# Omniboard.net
KiCad netlist of a schematic drawn in EAGLE
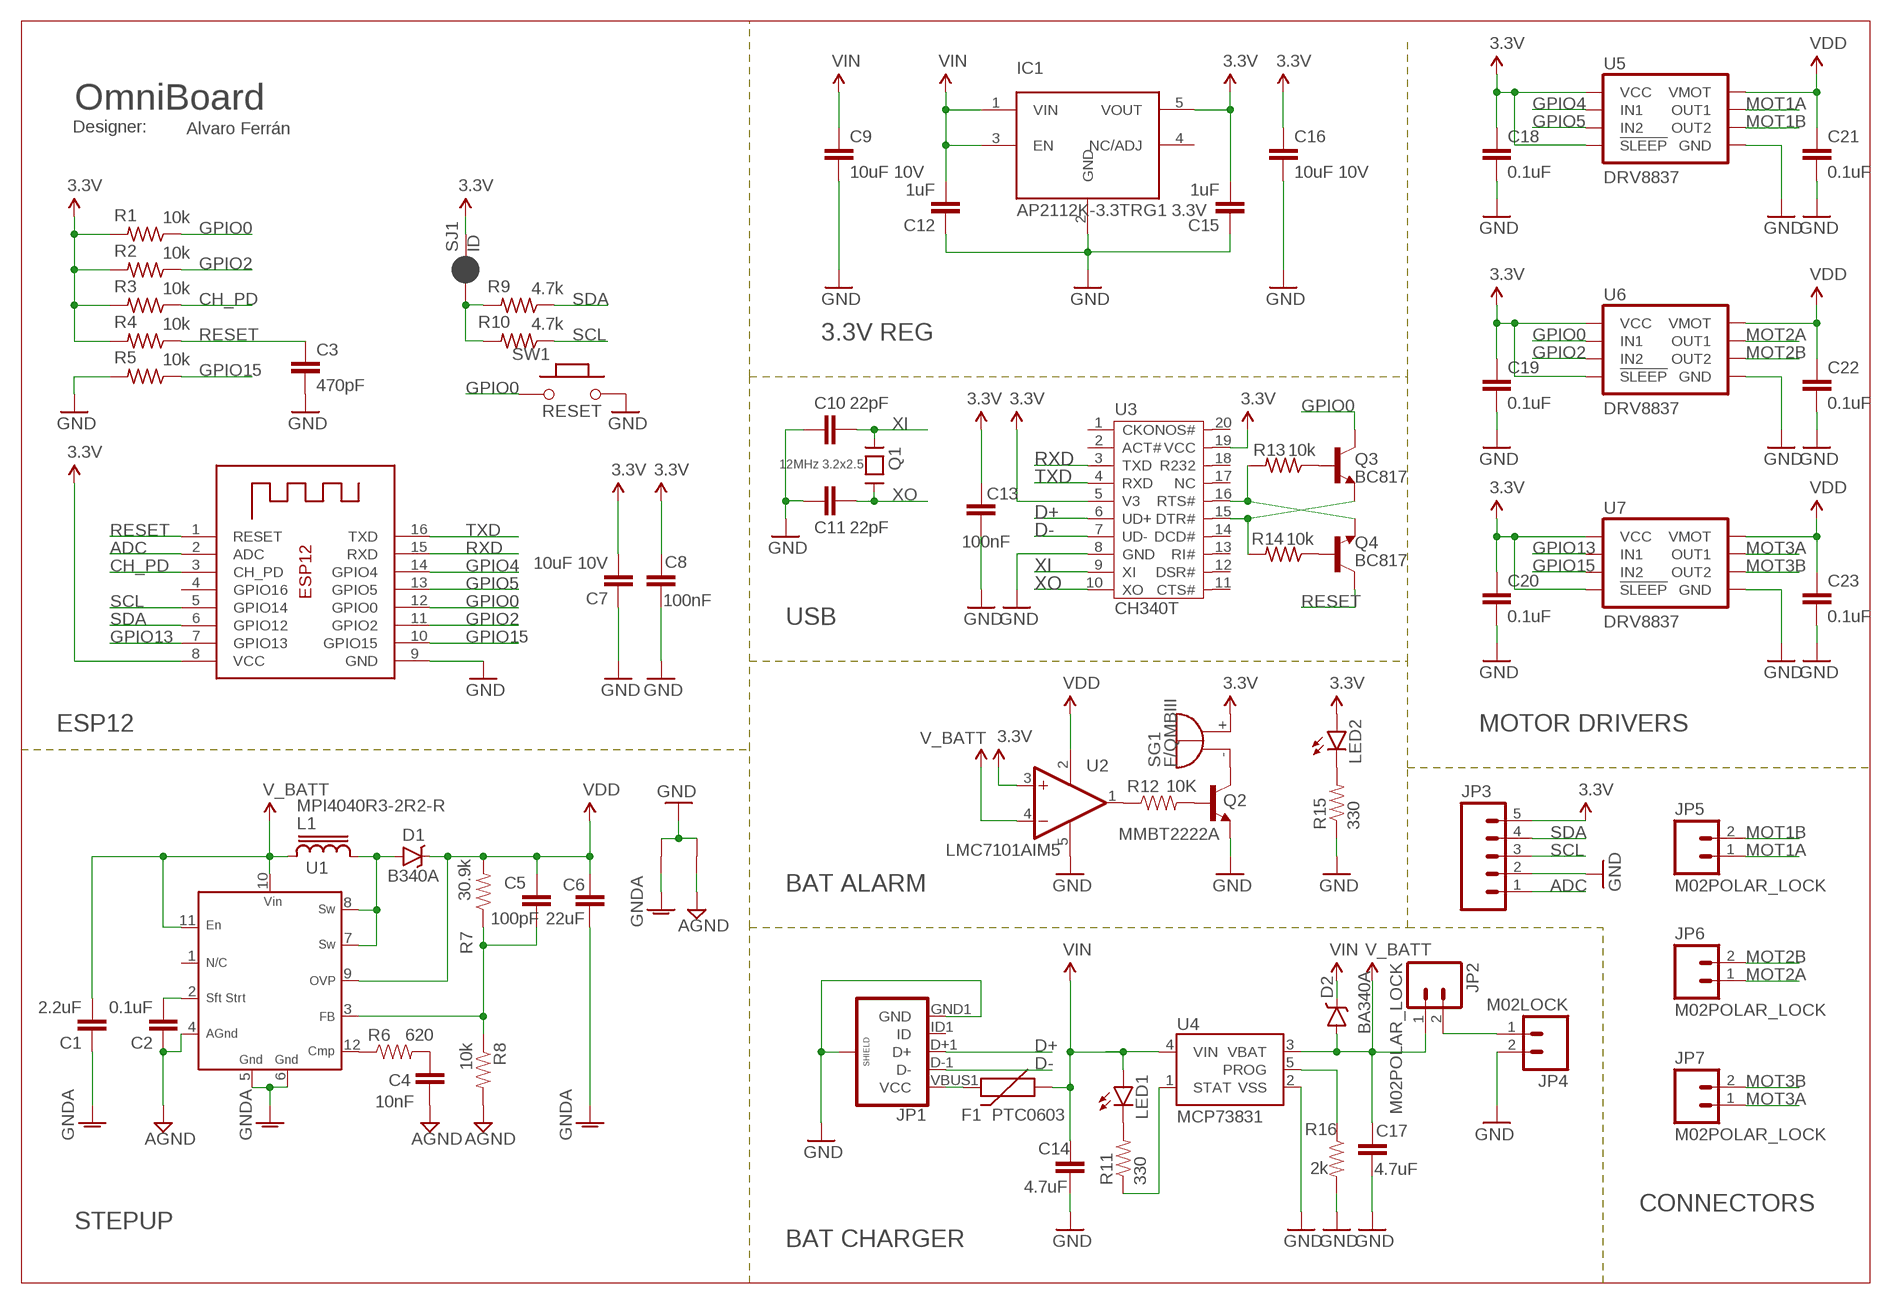
[diagram p0: schematic, sheet 1]

(export (version "E")
  (design (tool "Eeschema 10.0.6"))
  (components
    (comp (ref "C1")
      (value "2.2uF")
      (footprint "eagle-import:0603-CAP")
      (libsource (lib "eagle-import") (part "CAP0603-CAP"))
    )
    (comp (ref "C2")
      (value "0.1uF")
      (footprint "eagle-import:0603-CAP")
      (libsource (lib "eagle-import") (part "CAP0603-CAP"))
    )
    (comp (ref "C3")
      (value "470pF")
      (footprint "eagle-import:0402-CAP")
      (libsource (lib "eagle-import") (part "CAP0402-CAP"))
    )
    (comp (ref "C4")
      (value "10nF")
      (footprint "eagle-import:0603-CAP")
      (libsource (lib "eagle-import") (part "CAP0603-CAP"))
    )
    (comp (ref "C5")
      (value "100pF")
      (footprint "eagle-import:0603-CAP")
      (libsource (lib "eagle-import") (part "CAP0603-CAP"))
    )
    (comp (ref "C6")
      (value "22uF")
      (footprint "eagle-import:0805")
      (libsource (lib "eagle-import") (part "22UF-6.3V-20%(0805)"))
    )
    (comp (ref "C7")
      (value "10uF 10V")
      (footprint "eagle-import:0402-CAP")
      (libsource (lib "eagle-import") (part "CAP0402-CAP"))
    )
    (comp (ref "C8")
      (value "100nF")
      (footprint "eagle-import:0402-CAP")
      (libsource (lib "eagle-import") (part "CAP0402-CAP"))
    )
    (comp (ref "C9")
      (value "10uF 10V")
      (footprint "eagle-import:0603-CAP")
      (libsource (lib "eagle-import") (part "CAP0603-CAP"))
    )
    (comp (ref "C10")
      (value "22pF")
      (footprint "eagle-import:0402-CAP")
      (libsource (lib "eagle-import") (part "CAP0402-CAP"))
    )
    (comp (ref "C11")
      (value "22pF")
      (footprint "eagle-import:0402-CAP")
      (libsource (lib "eagle-import") (part "CAP0402-CAP"))
    )
    (comp (ref "C12")
      (value "1uF")
      (footprint "eagle-import:0603-CAP")
      (libsource (lib "eagle-import") (part "CAP0603-CAP"))
    )
    (comp (ref "C13")
      (value "100nF")
      (footprint "eagle-import:0402-CAP")
      (libsource (lib "eagle-import") (part "CAP0402-CAP"))
    )
    (comp (ref "C14")
      (value "4.7uF")
      (footprint "eagle-import:0402-CAP")
      (libsource (lib "eagle-import") (part "CAP0402-CAP"))
    )
    (comp (ref "C15")
      (value "1uF")
      (footprint "eagle-import:0603-CAP")
      (libsource (lib "eagle-import") (part "CAP0603-CAP"))
    )
    (comp (ref "C16")
      (value "10uF 10V")
      (footprint "eagle-import:0603-CAP")
      (libsource (lib "eagle-import") (part "CAP0603-CAP"))
    )
    (comp (ref "C17")
      (value "4.7uF")
      (footprint "eagle-import:0402-CAP")
      (libsource (lib "eagle-import") (part "CAP0402-CAP"))
    )
    (comp (ref "C18")
      (value "0.1uF")
      (footprint "eagle-import:0402-CAP")
      (libsource (lib "eagle-import") (part "0.1UF-16V(+-10%)(0402)"))
    )
    (comp (ref "C19")
      (value "0.1uF")
      (footprint "eagle-import:0402-CAP")
      (libsource (lib "eagle-import") (part "0.1UF-16V(+-10%)(0402)"))
    )
    (comp (ref "C20")
      (value "0.1uF")
      (footprint "eagle-import:0402-CAP")
      (libsource (lib "eagle-import") (part "0.1UF-16V(+-10%)(0402)"))
    )
    (comp (ref "C21")
      (value "0.1uF")
      (footprint "eagle-import:0402-CAP")
      (libsource (lib "eagle-import") (part "0.1UF-16V(+-10%)(0402)"))
    )
    (comp (ref "C22")
      (value "0.1uF")
      (footprint "eagle-import:0402-CAP")
      (libsource (lib "eagle-import") (part "0.1UF-16V(+-10%)(0402)"))
    )
    (comp (ref "C23")
      (value "0.1uF")
      (footprint "eagle-import:0402-CAP")
      (libsource (lib "eagle-import") (part "0.1UF-16V(+-10%)(0402)"))
    )
    (comp (ref "D1")
      (value "B340A")
      (footprint "eagle-import:SMA-DIODE")
      (libsource (lib "eagle-import") (part "DIODE-SCHOTTKY-B340A"))
    )
    (comp (ref "D2")
      (value "BA340A")
      (footprint "eagle-import:SMA-DIODE")
      (libsource (lib "eagle-import") (part "B340A"))
    )
    (comp (ref "F1")
      (value "PTC0603")
      (footprint "eagle-import:0603")
      (libsource (lib "eagle-import") (part "PTC0603"))
    )
    (comp (ref "GND10")
      (value "VIRTUAL_GND")
      (footprint "eagle-import:STARGND")
      (libsource (lib "eagle-import") (part "VIRTUAL_GND"))
    )
    (comp (ref "GND13")
      (value "VIRTUAL_GND")
      (footprint "eagle-import:STARGND")
      (libsource (lib "eagle-import") (part "VIRTUAL_GND"))
    )
    (comp (ref "IC1")
      (value "AP2112K-3.3TRG1 3.3V")
      (footprint "eagle-import:SOT23-5")
      (libsource (lib "eagle-import") (part "5PIN_REG"))
    )
    (comp (ref "JP1")
      (value "USB_MICROB")
      (footprint "eagle-import:USB-B-MICRO-SMD_V03")
      (libsource (lib "eagle-import") (part "USB_MICROB_PLUGCONN-11752"))
    )
    (comp (ref "JP2")
      (value "M02POLAR_LOCK")
      (footprint "eagle-import:MOLEX-1X2_LOCK")
      (libsource (lib "eagle-import") (part "M02POLAR_LOCK"))
    )
    (comp (ref "JP3")
      (value "M05LOCK")
      (footprint "eagle-import:1X05_LOCK")
      (libsource (lib "eagle-import") (part "M05LOCK"))
    )
    (comp (ref "JP4")
      (value "M02LOCK")
      (footprint "eagle-import:1X02_LOCK")
      (libsource (lib "eagle-import") (part "M02LOCK"))
    )
    (comp (ref "JP5")
      (value "M02POLAR_LOCK")
      (footprint "eagle-import:MOLEX-1X2_LOCK")
      (libsource (lib "eagle-import") (part "M02POLAR_LOCK"))
    )
    (comp (ref "JP6")
      (value "M02POLAR_LOCK")
      (footprint "eagle-import:MOLEX-1X2_LOCK")
      (libsource (lib "eagle-import") (part "M02POLAR_LOCK"))
    )
    (comp (ref "JP7")
      (value "M02POLAR_LOCK")
      (footprint "eagle-import:MOLEX-1X2_LOCK")
      (libsource (lib "eagle-import") (part "M02POLAR_LOCK"))
    )
    (comp (ref "L1")
      (value "MPI4040R3-2R2-R")
      (footprint "eagle-import:MPI4040R3-2R2-R")
      (libsource (lib "eagle-import") (part "MPI4040R3-2R2-R"))
    )
    (comp (ref "LED1")
      (value "LED0603")
      (footprint "eagle-import:LED-0603")
      (libsource (lib "eagle-import") (part "LED0603"))
    )
    (comp (ref "LED2")
      (value "LED0603")
      (footprint "eagle-import:LED-0603")
      (libsource (lib "eagle-import") (part "LED0603"))
    )
    (comp (ref "Q1")
      (value "12MHz 3.2x2.5")
      (footprint "eagle-import:CRYSTAL_3.2X2.5")
      (libsource (lib "eagle-import") (part "CRYSTAL3.2X2.5"))
    )
    (comp (ref "Q2")
      (value "MMBT2222A")
      (footprint "eagle-import:SOT23-3")
      (libsource (lib "eagle-import") (part "TRANSISTOR_NPNMMBT2222A"))
    )
    (comp (ref "Q3")
      (value "BC817")
      (footprint "eagle-import:SOT23-BEC")
      (libsource (lib "eagle-import") (part "BC817SMD-16"))
    )
    (comp (ref "Q4")
      (value "BC817")
      (footprint "eagle-import:SOT23-BEC")
      (libsource (lib "eagle-import") (part "BC817SMD-16"))
    )
    (comp (ref "R1")
      (value "10k")
      (footprint "eagle-import:R0402")
      (libsource (lib "eagle-import") (part "R-US_R0402"))
    )
    (comp (ref "R2")
      (value "10k")
      (footprint "eagle-import:R0402")
      (libsource (lib "eagle-import") (part "R-US_R0402"))
    )
    (comp (ref "R3")
      (value "10k")
      (footprint "eagle-import:R0402")
      (libsource (lib "eagle-import") (part "R-US_R0402"))
    )
    (comp (ref "R4")
      (value "10k")
      (footprint "eagle-import:R0402")
      (libsource (lib "eagle-import") (part "R-US_R0402"))
    )
    (comp (ref "R5")
      (value "10k")
      (footprint "eagle-import:R0402")
      (libsource (lib "eagle-import") (part "R-US_R0402"))
    )
    (comp (ref "R6")
      (value "620")
      (footprint "eagle-import:0603-RES")
      (libsource (lib "eagle-import") (part "SparkFun-Passives_RESISTOR0603-RES"))
    )
    (comp (ref "R7")
      (value "30.9k")
      (footprint "eagle-import:0603-RES")
      (libsource (lib "eagle-import") (part "SparkFun-Passives_RESISTOR0603-RES"))
    )
    (comp (ref "R8")
      (value "10k")
      (footprint "eagle-import:0603-RES")
      (libsource (lib "eagle-import") (part "SparkFun-Passives_RESISTOR0603-RES"))
    )
    (comp (ref "R9")
      (value "4.7k")
      (footprint "eagle-import:R0402")
      (libsource (lib "eagle-import") (part "R-US_R0402"))
    )
    (comp (ref "R10")
      (value "4.7k")
      (footprint "eagle-import:R0402")
      (libsource (lib "eagle-import") (part "R-US_R0402"))
    )
    (comp (ref "R11")
      (value "330")
      (footprint "eagle-import:0402-RES")
      (libsource (lib "eagle-import") (part "SparkFun-Passives_RESISTOR0402-RES"))
    )
    (comp (ref "R12")
      (value "10K")
      (footprint "eagle-import:0402-RES")
      (libsource (lib "eagle-import") (part "RESISTOR0402-RES"))
    )
    (comp (ref "R13")
      (value "10k")
      (footprint "eagle-import:R0402")
      (libsource (lib "eagle-import") (part "R-US_R0402"))
    )
    (comp (ref "R14")
      (value "10k")
      (footprint "eagle-import:R0402")
      (libsource (lib "eagle-import") (part "R-US_R0402"))
    )
    (comp (ref "R15")
      (value "330")
      (footprint "eagle-import:0402-RES")
      (libsource (lib "eagle-import") (part "SparkFun-Passives_RESISTOR0402-RES"))
    )
    (comp (ref "R16")
      (value "2k")
      (footprint "eagle-import:0402-RES")
      (libsource (lib "eagle-import") (part "SparkFun-Passives_RESISTOR0402-RES"))
    )
    (comp (ref "SG1")
      (value "F/QMBIII")
      (footprint "eagle-import:F_QMBIII")
      (libsource (lib "eagle-import") (part "F/QMBIII"))
    )
    (comp (ref "SJ1")
      (value "ID")
      (footprint "eagle-import:PAD-JUMPER-2-NC_BY_PASTE_YES_SILK")
      (libsource (lib "eagle-import") (part "JUMPER-PAD-2-NC_BY_PASTE"))
    )
    (comp (ref "SW1")
      (value "RESET")
      (footprint "eagle-import:157SW")
      (libsource (lib "eagle-import") (part "PB157"))
    )
    (comp (ref "U1")
      (value "MIC2253")
      (footprint "eagle-import:MLF12_3.0MM_X_3.0MM")
      (libsource (lib "eagle-import") (part "MIC2253"))
    )
    (comp (ref "U2")
      (value "LMC7101AIM5")
      (footprint "eagle-import:SOT23-5")
      (libsource (lib "eagle-import") (part "LMC7101AIM5"))
    )
    (comp (ref "U3")
      (value "CH340T")
      (footprint "eagle-import:SSOP20")
      (libsource (lib "eagle-import") (part "CH340T"))
    )
    (comp (ref "U4")
      (value "MCP73831")
      (footprint "eagle-import:SOT23-5")
      (libsource (lib "eagle-import") (part "MCP73831"))
    )
    (comp (ref "U5")
      (value "DRV8837")
      (footprint "eagle-import:DSG")
      (libsource (lib "eagle-import") (part "DRV8837"))
    )
    (comp (ref "U6")
      (value "DRV8837")
      (footprint "eagle-import:DSG")
      (libsource (lib "eagle-import") (part "DRV8837"))
    )
    (comp (ref "U7")
      (value "DRV8837")
      (footprint "eagle-import:DSG")
      (libsource (lib "eagle-import") (part "DRV8837"))
    )
    (comp (ref "X1")
      (value "ESP-12")
      (footprint "eagle-import:ESP-12")
      (libsource (lib "eagle-import") (part "ESP-12"))
    )
  )
  (nets
    (net (code "1") (name "/ADC") (class "Default")
      (node (ref "JP3") (pin "1") (pinfunction "1_1") (pintype "passive"))
      (node (ref "X1") (pin "2") (pinfunction "ADC_2") (pintype "passive"))
    )
    (net (code "2") (name "/CH_PD") (class "Default")
      (node (ref "R3") (pin "1") (pinfunction "1_1") (pintype "passive"))
      (node (ref "X1") (pin "3") (pinfunction "CH_PD_3") (pintype "input"))
    )
    (net (code "3") (name "/D+") (class "Default")
      (node (ref "JP1") (pin "D+1") (pinfunction "D+_D+1") (pintype "bidirectional"))
      (node (ref "U3") (pin "6") (pinfunction "UD+_6") (pintype "bidirectional"))
    )
    (net (code "4") (name "/D-") (class "Default")
      (node (ref "JP1") (pin "D-1") (pinfunction "D-_D-1") (pintype "bidirectional"))
      (node (ref "U3") (pin "7") (pinfunction "UD-_7") (pintype "bidirectional"))
    )
    (net (code "5") (name "/GPIO0") (class "Default")
      (node (ref "Q3") (pin "C") (pinfunction "C_C") (pintype "passive"))
      (node (ref "R1") (pin "1") (pinfunction "1_1") (pintype "passive"))
      (node (ref "SW1") (pin "1") (pinfunction "1_1") (pintype "passive"))
      (node (ref "U6") (pin "6") (pinfunction "IN1_6") (pintype "bidirectional"))
      (node (ref "X1") (pin "12") (pinfunction "GPIO0_12") (pintype "bidirectional"))
    )
    (net (code "6") (name "/GPIO2") (class "Default")
      (node (ref "R2") (pin "1") (pinfunction "1_1") (pintype "passive"))
      (node (ref "U6") (pin "5") (pinfunction "IN2_5") (pintype "bidirectional"))
      (node (ref "X1") (pin "11") (pinfunction "GPIO2_11") (pintype "bidirectional"))
    )
    (net (code "7") (name "/GPIO4") (class "Default")
      (node (ref "U5") (pin "6") (pinfunction "IN1_6") (pintype "bidirectional"))
      (node (ref "X1") (pin "14") (pinfunction "GPIO4_14") (pintype "bidirectional"))
    )
    (net (code "8") (name "/GPIO5") (class "Default")
      (node (ref "U5") (pin "5") (pinfunction "IN2_5") (pintype "bidirectional"))
      (node (ref "X1") (pin "13") (pinfunction "GPIO5_13") (pintype "bidirectional"))
    )
    (net (code "9") (name "/GPIO13") (class "Default")
      (node (ref "U7") (pin "6") (pinfunction "IN1_6") (pintype "bidirectional"))
      (node (ref "X1") (pin "7") (pinfunction "GPIO13_7") (pintype "bidirectional"))
    )
    (net (code "10") (name "/GPIO15") (class "Default")
      (node (ref "R5") (pin "1") (pinfunction "1_1") (pintype "passive"))
      (node (ref "U7") (pin "5") (pinfunction "IN2_5") (pintype "bidirectional"))
      (node (ref "X1") (pin "10") (pinfunction "GPIO15_10") (pintype "bidirectional"))
    )
    (net (code "11") (name "/MOT1A") (class "Default")
      (node (ref "JP5") (pin "1") (pinfunction "1_1") (pintype "passive"))
      (node (ref "U5") (pin "2") (pinfunction "OUT1_2") (pintype "bidirectional"))
    )
    (net (code "12") (name "/MOT1B") (class "Default")
      (node (ref "JP5") (pin "2") (pinfunction "2_2") (pintype "passive"))
      (node (ref "U5") (pin "3") (pinfunction "OUT2_3") (pintype "bidirectional"))
    )
    (net (code "13") (name "/MOT2A") (class "Default")
      (node (ref "JP6") (pin "1") (pinfunction "1_1") (pintype "passive"))
      (node (ref "U6") (pin "2") (pinfunction "OUT1_2") (pintype "bidirectional"))
    )
    (net (code "14") (name "/MOT2B") (class "Default")
      (node (ref "JP6") (pin "2") (pinfunction "2_2") (pintype "passive"))
      (node (ref "U6") (pin "3") (pinfunction "OUT2_3") (pintype "bidirectional"))
    )
    (net (code "15") (name "/MOT3A") (class "Default")
      (node (ref "JP7") (pin "1") (pinfunction "1_1") (pintype "passive"))
      (node (ref "U7") (pin "2") (pinfunction "OUT1_2") (pintype "bidirectional"))
    )
    (net (code "16") (name "/MOT3B") (class "Default")
      (node (ref "JP7") (pin "2") (pinfunction "2_2") (pintype "passive"))
      (node (ref "U7") (pin "3") (pinfunction "OUT2_3") (pintype "bidirectional"))
    )
    (net (code "17") (name "/NOS#") (class "Default")
      (node (ref "U3") (pin "20") (pinfunction "NOS#_20") (pintype "power_in"))
    )
    (net (code "18") (name "/RESET") (class "Default")
      (node (ref "C3") (pin "1") (pinfunction "1_1") (pintype "passive"))
      (node (ref "Q4") (pin "C") (pinfunction "C_C") (pintype "passive"))
      (node (ref "R4") (pin "1") (pinfunction "1_1") (pintype "passive"))
      (node (ref "X1") (pin "1") (pinfunction "RESET_1") (pintype "input"))
    )
    (net (code "19") (name "/RXD") (class "Default")
      (node (ref "U3") (pin "3") (pinfunction "TXD_3") (pintype "output"))
      (node (ref "X1") (pin "15") (pinfunction "RXD_15") (pintype "input"))
    )
    (net (code "20") (name "/SCL") (class "Default")
      (node (ref "JP3") (pin "3") (pinfunction "3_3") (pintype "passive"))
      (node (ref "R10") (pin "1") (pinfunction "1_1") (pintype "passive"))
      (node (ref "X1") (pin "5") (pinfunction "GPIO14_5") (pintype "bidirectional"))
    )
    (net (code "21") (name "/SDA") (class "Default")
      (node (ref "JP3") (pin "4") (pinfunction "4_4") (pintype "passive"))
      (node (ref "R9") (pin "1") (pinfunction "1_1") (pintype "passive"))
      (node (ref "X1") (pin "6") (pinfunction "GPIO12_6") (pintype "bidirectional"))
    )
    (net (code "22") (name "/TXD") (class "Default")
      (node (ref "U3") (pin "4") (pinfunction "RXD_4") (pintype "input"))
      (node (ref "X1") (pin "16") (pinfunction "TXD_16") (pintype "output"))
    )
    (net (code "23") (name "/XI") (class "Default")
      (node (ref "C10") (pin "2") (pinfunction "2_2") (pintype "passive"))
      (node (ref "Q1") (pin "3") (pinfunction "P$2_3") (pintype "passive"))
      (node (ref "U3") (pin "9") (pinfunction "XI_9") (pintype "input"))
    )
    (net (code "24") (name "/XO") (class "Default")
      (node (ref "C11") (pin "2") (pinfunction "2_2") (pintype "passive"))
      (node (ref "Q1") (pin "1") (pinfunction "P$1_1") (pintype "passive"))
      (node (ref "U3") (pin "10") (pinfunction "XO_10") (pintype "output"))
    )
    (net (code "25") (name "3.3V") (class "Default")
      (node (ref "C13") (pin "2") (pinfunction "2_2") (pintype "passive"))
      (node (ref "C15") (pin "2") (pinfunction "2_2") (pintype "passive"))
      (node (ref "C16") (pin "1") (pinfunction "1_1") (pintype "passive"))
      (node (ref "C18") (pin "1") (pinfunction "1_1") (pintype "passive"))
      (node (ref "C19") (pin "1") (pinfunction "1_1") (pintype "passive"))
      (node (ref "C20") (pin "1") (pinfunction "1_1") (pintype "passive"))
      (node (ref "C7") (pin "2") (pinfunction "2_2") (pintype "passive"))
      (node (ref "C8") (pin "1") (pinfunction "1_1") (pintype "passive"))
      (node (ref "IC1") (pin "5") (pinfunction "VOUT_5") (pintype "bidirectional"))
      (node (ref "JP3") (pin "5") (pinfunction "5_5") (pintype "passive"))
      (node (ref "LED2") (pin "A") (pinfunction "A_A") (pintype "passive"))
      (node (ref "R1") (pin "2") (pinfunction "2_2") (pintype "passive"))
      (node (ref "R2") (pin "2") (pinfunction "2_2") (pintype "passive"))
      (node (ref "R3") (pin "2") (pinfunction "2_2") (pintype "passive"))
      (node (ref "R4") (pin "2") (pinfunction "2_2") (pintype "passive"))
      (node (ref "SG1") (pin "+") (pinfunction "-_+") (pintype "passive"))
      (node (ref "SJ1") (pin "2") (pinfunction "2_2") (pintype "passive"))
      (node (ref "U2") (pin "3") (pinfunction "+IN_3") (pintype "input"))
      (node (ref "U3") (pin "19") (pinfunction "VCC_19") (pintype "power_in"))
      (node (ref "U3") (pin "5") (pinfunction "V3_5") (pintype "power_in"))
      (node (ref "U5") (pin "7") (pinfunction "~{SLEEP}_7") (pintype "bidirectional"))
      (node (ref "U5") (pin "8") (pinfunction "VCC_8") (pintype "bidirectional"))
      (node (ref "U6") (pin "7") (pinfunction "~{SLEEP}_7") (pintype "bidirectional"))
      (node (ref "U6") (pin "8") (pinfunction "VCC_8") (pintype "bidirectional"))
      (node (ref "U7") (pin "7") (pinfunction "~{SLEEP}_7") (pintype "bidirectional"))
      (node (ref "U7") (pin "8") (pinfunction "VCC_8") (pintype "bidirectional"))
      (node (ref "X1") (pin "8") (pinfunction "VCC_8") (pintype "power_in"))
    )
    (net (code "26") (name "AGND") (class "Default")
      (node (ref "C2") (pin "1") (pinfunction "1_1") (pintype "passive"))
      (node (ref "C4") (pin "1") (pinfunction "1_1") (pintype "passive"))
      (node (ref "GND13") (pin "P$1") (pinfunction "P$1_P$1") (pintype "bidirectional"))
      (node (ref "R8") (pin "2") (pinfunction "2_2") (pintype "passive"))
      (node (ref "U1") (pin "4") (pinfunction "AGND_4") (pintype "passive"))
    )
    (net (code "27") (name "GND") (class "Default")
      (node (ref "C10") (pin "1") (pinfunction "1_1") (pintype "passive"))
      (node (ref "C11") (pin "1") (pinfunction "1_1") (pintype "passive"))
      (node (ref "C12") (pin "1") (pinfunction "1_1") (pintype "passive"))
      (node (ref "C13") (pin "1") (pinfunction "1_1") (pintype "passive"))
      (node (ref "C14") (pin "2") (pinfunction "2_2") (pintype "passive"))
      (node (ref "C15") (pin "1") (pinfunction "1_1") (pintype "passive"))
      (node (ref "C16") (pin "2") (pinfunction "2_2") (pintype "passive"))
      (node (ref "C17") (pin "2") (pinfunction "2_2") (pintype "passive"))
      (node (ref "C18") (pin "2") (pinfunction "2_2") (pintype "passive"))
      (node (ref "C19") (pin "2") (pinfunction "2_2") (pintype "passive"))
      (node (ref "C20") (pin "2") (pinfunction "2_2") (pintype "passive"))
      (node (ref "C21") (pin "2") (pinfunction "2_2") (pintype "passive"))
      (node (ref "C22") (pin "2") (pinfunction "2_2") (pintype "passive"))
      (node (ref "C23") (pin "2") (pinfunction "2_2") (pintype "passive"))
      (node (ref "C3") (pin "2") (pinfunction "2_2") (pintype "passive"))
      (node (ref "C7") (pin "1") (pinfunction "1_1") (pintype "passive"))
      (node (ref "C8") (pin "2") (pinfunction "2_2") (pintype "passive"))
      (node (ref "C9") (pin "2") (pinfunction "2_2") (pintype "passive"))
      (node (ref "GND10") (pin "P$2") (pinfunction "P$2_P$2") (pintype "bidirectional"))
      (node (ref "GND13") (pin "P$2") (pinfunction "P$2_P$2") (pintype "bidirectional"))
      (node (ref "IC1") (pin "2") (pinfunction "GND_2") (pintype "bidirectional"))
      (node (ref "JP1") (pin "GND1") (pinfunction "GND_GND1") (pintype "bidirectional"))
      (node (ref "JP1") (pin "SHIELD1") (pinfunction "SHIELD_SHIELD1") (pintype "bidirectional"))
      (node (ref "JP1") (pin "SHIELD2") (pinfunction "SHIELD_SHIELD2") (pintype "bidirectional"))
      (node (ref "JP1") (pin "SHIELD3") (pinfunction "SHIELD_SHIELD3") (pintype "bidirectional"))
      (node (ref "JP3") (pin "2") (pinfunction "2_2") (pintype "passive"))
      (node (ref "JP4") (pin "2") (pinfunction "2_2") (pintype "passive"))
      (node (ref "Q2") (pin "2") (pinfunction "E_2") (pintype "passive"))
      (node (ref "R15") (pin "1") (pinfunction "1_1") (pintype "passive"))
      (node (ref "R16") (pin "2") (pinfunction "2_2") (pintype "passive"))
      (node (ref "R5") (pin "2") (pinfunction "2_2") (pintype "passive"))
      (node (ref "SW1") (pin "2") (pinfunction "2_2") (pintype "passive"))
      (node (ref "U2") (pin "5") (pinfunction "V-_5") (pintype "power_in"))
      (node (ref "U3") (pin "8") (pinfunction "GND_8") (pintype "power_in"))
      (node (ref "U4") (pin "2") (pinfunction "VSS_2") (pintype "power_in"))
      (node (ref "U5") (pin "4") (pinfunction "GND_4") (pintype "bidirectional"))
      (node (ref "U5") (pin "PAD") (pinfunction "GND_PAD") (pintype "bidirectional"))
      (node (ref "U6") (pin "4") (pinfunction "GND_4") (pintype "bidirectional"))
      (node (ref "U6") (pin "PAD") (pinfunction "GND_PAD") (pintype "bidirectional"))
      (node (ref "U7") (pin "4") (pinfunction "GND_4") (pintype "bidirectional"))
      (node (ref "U7") (pin "PAD") (pinfunction "GND_PAD") (pintype "bidirectional"))
      (node (ref "X1") (pin "9") (pinfunction "GND_9") (pintype "power_in"))
    )
    (net (code "28") (name "GNDA") (class "Default")
      (node (ref "C1") (pin "1") (pinfunction "1_1") (pintype "passive"))
      (node (ref "C6") (pin "1") (pinfunction "1_1") (pintype "passive"))
      (node (ref "GND10") (pin "P$1") (pinfunction "P$1_P$1") (pintype "bidirectional"))
      (node (ref "U1") (pin "5") (pinfunction "GND_5") (pintype "passive"))
      (node (ref "U1") (pin "6") (pinfunction "GND_6") (pintype "passive"))
    )
    (net (code "29") (name "Net-(C4-Pad2)") (class "Default")
      (node (ref "C4") (pin "2") (pinfunction "2_2") (pintype "passive"))
      (node (ref "R6") (pin "2") (pinfunction "2_2") (pintype "passive"))
    )
    (net (code "30") (name "Net-(JP1-VCC)") (class "Default")
      (node (ref "F1") (pin "2") (pinfunction "2_2") (pintype "bidirectional"))
      (node (ref "JP1") (pin "VBUS1") (pinfunction "VCC_VBUS1") (pintype "bidirectional"))
    )
    (net (code "31") (name "Net-(JP2-Pad2)") (class "Default")
      (node (ref "JP2") (pin "2") (pinfunction "2_2") (pintype "passive"))
      (node (ref "JP4") (pin "1") (pinfunction "1_1") (pintype "passive"))
    )
    (net (code "32") (name "Net-(L1-2)") (class "Default")
      (node (ref "D1") (pin "A") (pinfunction "A_A") (pintype "passive"))
      (node (ref "L1") (pin "P$2") (pinfunction "2_P$2") (pintype "passive"))
      (node (ref "U1") (pin "7") (pinfunction "SW_7") (pintype "open_collector"))
      (node (ref "U1") (pin "8") (pinfunction "SW_8") (pintype "open_collector"))
    )
    (net (code "33") (name "Net-(LED1-PadC)") (class "Default")
      (node (ref "LED1") (pin "C") (pinfunction "C_C") (pintype "passive"))
      (node (ref "R11") (pin "2") (pinfunction "2_2") (pintype "passive"))
    )
    (net (code "34") (name "Net-(LED2-PadC)") (class "Default")
      (node (ref "LED2") (pin "C") (pinfunction "C_C") (pintype "passive"))
      (node (ref "R15") (pin "2") (pinfunction "2_2") (pintype "passive"))
    )
    (net (code "35") (name "Net-(Q2-B)") (class "Default")
      (node (ref "Q2") (pin "1") (pinfunction "B_1") (pintype "passive"))
      (node (ref "R12") (pin "2") (pinfunction "2_2") (pintype "passive"))
    )
    (net (code "36") (name "Net-(Q2-C)") (class "Default")
      (node (ref "Q2") (pin "3") (pinfunction "C_3") (pintype "passive"))
      (node (ref "SG1") (pin "-") (pinfunction "+_-") (pintype "passive"))
    )
    (net (code "37") (name "Net-(Q3-PadB)") (class "Default")
      (node (ref "Q3") (pin "B") (pinfunction "B_B") (pintype "passive"))
      (node (ref "R13") (pin "1") (pinfunction "1_1") (pintype "passive"))
    )
    (net (code "38") (name "Net-(Q4-PadB)") (class "Default")
      (node (ref "Q4") (pin "B") (pinfunction "B_B") (pintype "passive"))
      (node (ref "R14") (pin "1") (pinfunction "1_1") (pintype "passive"))
    )
    (net (code "39") (name "Net-(R10-Pad2)") (class "Default")
      (node (ref "R10") (pin "2") (pinfunction "2_2") (pintype "passive"))
      (node (ref "R9") (pin "2") (pinfunction "2_2") (pintype "passive"))
      (node (ref "SJ1") (pin "1") (pinfunction "1_1") (pintype "passive"))
    )
    (net (code "40") (name "Net-(U1-CMP)") (class "Default")
      (node (ref "R6") (pin "1") (pinfunction "1_1") (pintype "passive"))
      (node (ref "U1") (pin "12") (pinfunction "CMP_12") (pintype "passive"))
    )
    (net (code "41") (name "Net-(U1-FB)") (class "Default")
      (node (ref "C5") (pin "1") (pinfunction "1_1") (pintype "passive"))
      (node (ref "R7") (pin "1") (pinfunction "1_1") (pintype "passive"))
      (node (ref "R8") (pin "1") (pinfunction "1_1") (pintype "passive"))
      (node (ref "U1") (pin "3") (pinfunction "FB_3") (pintype "passive"))
    )
    (net (code "42") (name "Net-(U1-SS)") (class "Default")
      (node (ref "C2") (pin "2") (pinfunction "2_2") (pintype "passive"))
      (node (ref "U1") (pin "2") (pinfunction "SS_2") (pintype "passive"))
    )
    (net (code "43") (name "Net-(U2-OUT)") (class "Default")
      (node (ref "R12") (pin "1") (pinfunction "1_1") (pintype "passive"))
      (node (ref "U2") (pin "1") (pinfunction "OUT_1") (pintype "output"))
    )
    (net (code "44") (name "Net-(U3-DTR#)") (class "Default")
      (node (ref "Q3") (pin "E") (pinfunction "E_E") (pintype "passive"))
      (node (ref "R14") (pin "2") (pinfunction "2_2") (pintype "passive"))
      (node (ref "U3") (pin "15") (pinfunction "DTR#_15") (pintype "output"))
    )
    (net (code "45") (name "Net-(U3-RTS#)") (class "Default")
      (node (ref "Q4") (pin "E") (pinfunction "E_E") (pintype "passive"))
      (node (ref "R13") (pin "2") (pinfunction "2_2") (pintype "passive"))
      (node (ref "U3") (pin "16") (pinfunction "RTS#_16") (pintype "output"))
    )
    (net (code "46") (name "Net-(U4-PROG)") (class "Default")
      (node (ref "R16") (pin "1") (pinfunction "1_1") (pintype "passive"))
      (node (ref "U4") (pin "5") (pinfunction "PROG_5") (pintype "input"))
    )
    (net (code "47") (name "Net-(U4-STAT)") (class "Default")
      (node (ref "R11") (pin "1") (pinfunction "1_1") (pintype "passive"))
      (node (ref "U4") (pin "1") (pinfunction "STAT_1") (pintype "output"))
    )
    (net (code "48") (name "VDD") (class "Default")
      (node (ref "C21") (pin "1") (pinfunction "1_1") (pintype "passive"))
      (node (ref "C22") (pin "1") (pinfunction "1_1") (pintype "passive"))
      (node (ref "C23") (pin "1") (pinfunction "1_1") (pintype "passive"))
      (node (ref "C5") (pin "2") (pinfunction "2_2") (pintype "passive"))
      (node (ref "C6") (pin "2") (pinfunction "2_2") (pintype "passive"))
      (node (ref "D1") (pin "C") (pinfunction "C_C") (pintype "passive"))
      (node (ref "R7") (pin "2") (pinfunction "2_2") (pintype "passive"))
      (node (ref "U1") (pin "9") (pinfunction "OVP_9") (pintype "passive"))
      (node (ref "U2") (pin "2") (pinfunction "V+_2") (pintype "power_in"))
      (node (ref "U5") (pin "1") (pinfunction "VMOT_1") (pintype "bidirectional"))
      (node (ref "U6") (pin "1") (pinfunction "VMOT_1") (pintype "bidirectional"))
      (node (ref "U7") (pin "1") (pinfunction "VMOT_1") (pintype "bidirectional"))
    )
    (net (code "49") (name "VIN") (class "Default")
      (node (ref "C12") (pin "2") (pinfunction "2_2") (pintype "passive"))
      (node (ref "C14") (pin "1") (pinfunction "1_1") (pintype "passive"))
      (node (ref "C9") (pin "1") (pinfunction "1_1") (pintype "passive"))
      (node (ref "D2") (pin "C") (pinfunction "C_C") (pintype "passive"))
      (node (ref "F1") (pin "1") (pinfunction "1_1") (pintype "bidirectional"))
      (node (ref "IC1") (pin "1") (pinfunction "VIN_1") (pintype "bidirectional"))
      (node (ref "IC1") (pin "3") (pinfunction "EN_3") (pintype "bidirectional"))
      (node (ref "LED1") (pin "A") (pinfunction "A_A") (pintype "passive"))
      (node (ref "U4") (pin "4") (pinfunction "VIN_4") (pintype "power_in"))
    )
    (net (code "50") (name "V_BATT") (class "Default")
      (node (ref "C1") (pin "2") (pinfunction "2_2") (pintype "passive"))
      (node (ref "C17") (pin "1") (pinfunction "1_1") (pintype "passive"))
      (node (ref "D2") (pin "A") (pinfunction "A_A") (pintype "passive"))
      (node (ref "JP2") (pin "1") (pinfunction "1_1") (pintype "passive"))
      (node (ref "L1") (pin "P$1") (pinfunction "1_P$1") (pintype "passive"))
      (node (ref "U1") (pin "10") (pinfunction "VIN_10") (pintype "passive"))
      (node (ref "U1") (pin "11") (pinfunction "EN_11") (pintype "input"))
      (node (ref "U2") (pin "4") (pinfunction "-IN_4") (pintype "input"))
      (node (ref "U4") (pin "3") (pinfunction "VBAT_3") (pintype "power_in"))
    )
    (net (code "51") (name "unconnected-(IC1-NC{slash}ADJ-Pad4)") (class "Default")
      (node (ref "IC1") (pin "4") (pinfunction "NC/ADJ_4") (pintype "bidirectional"))
    )
    (net (code "52") (name "unconnected-(JP1-ID-PadID1)") (class "Default")
      (node (ref "JP1") (pin "ID1") (pinfunction "ID_ID1") (pintype "bidirectional"))
    )
    (net (code "53") (name "unconnected-(U1-NC-Pad1)") (class "Default")
      (node (ref "U1") (pin "1") (pinfunction "NC_1") (pintype "no_connect"))
    )
    (net (code "54") (name "unconnected-(U3-ACT#-Pad2)") (class "Default")
      (node (ref "U3") (pin "2") (pinfunction "ACT#_2") (pintype "output"))
    )
    (net (code "55") (name "unconnected-(U3-CKO-Pad1)") (class "Default")
      (node (ref "U3") (pin "1") (pinfunction "CKO_1") (pintype "output"))
    )
    (net (code "56") (name "unconnected-(U3-CTS#-Pad11)") (class "Default")
      (node (ref "U3") (pin "11") (pinfunction "CTS#_11") (pintype "input"))
    )
    (net (code "57") (name "unconnected-(U3-DCD#-Pad14)") (class "Default")
      (node (ref "U3") (pin "14") (pinfunction "DCD#_14") (pintype "input"))
    )
    (net (code "58") (name "unconnected-(U3-DSR#-Pad12)") (class "Default")
      (node (ref "U3") (pin "12") (pinfunction "DSR#_12") (pintype "input"))
    )
    (net (code "59") (name "unconnected-(U3-NC-Pad17)") (class "Default")
      (node (ref "U3") (pin "17") (pinfunction "NC_17") (pintype "no_connect"))
    )
    (net (code "60") (name "unconnected-(U3-R232-Pad18)") (class "Default")
      (node (ref "U3") (pin "18") (pinfunction "R232_18") (pintype "input"))
    )
    (net (code "61") (name "unconnected-(U3-RI#-Pad13)") (class "Default")
      (node (ref "U3") (pin "13") (pinfunction "RI#_13") (pintype "input"))
    )
    (net (code "62") (name "unconnected-(X1-GPIO16-Pad4)") (class "Default")
      (node (ref "X1") (pin "4") (pinfunction "GPIO16_4") (pintype "bidirectional"))
    )
  )
)
